# VM_Motor_v2_1.net
KiCad netlist of a schematic drawn in EAGLE
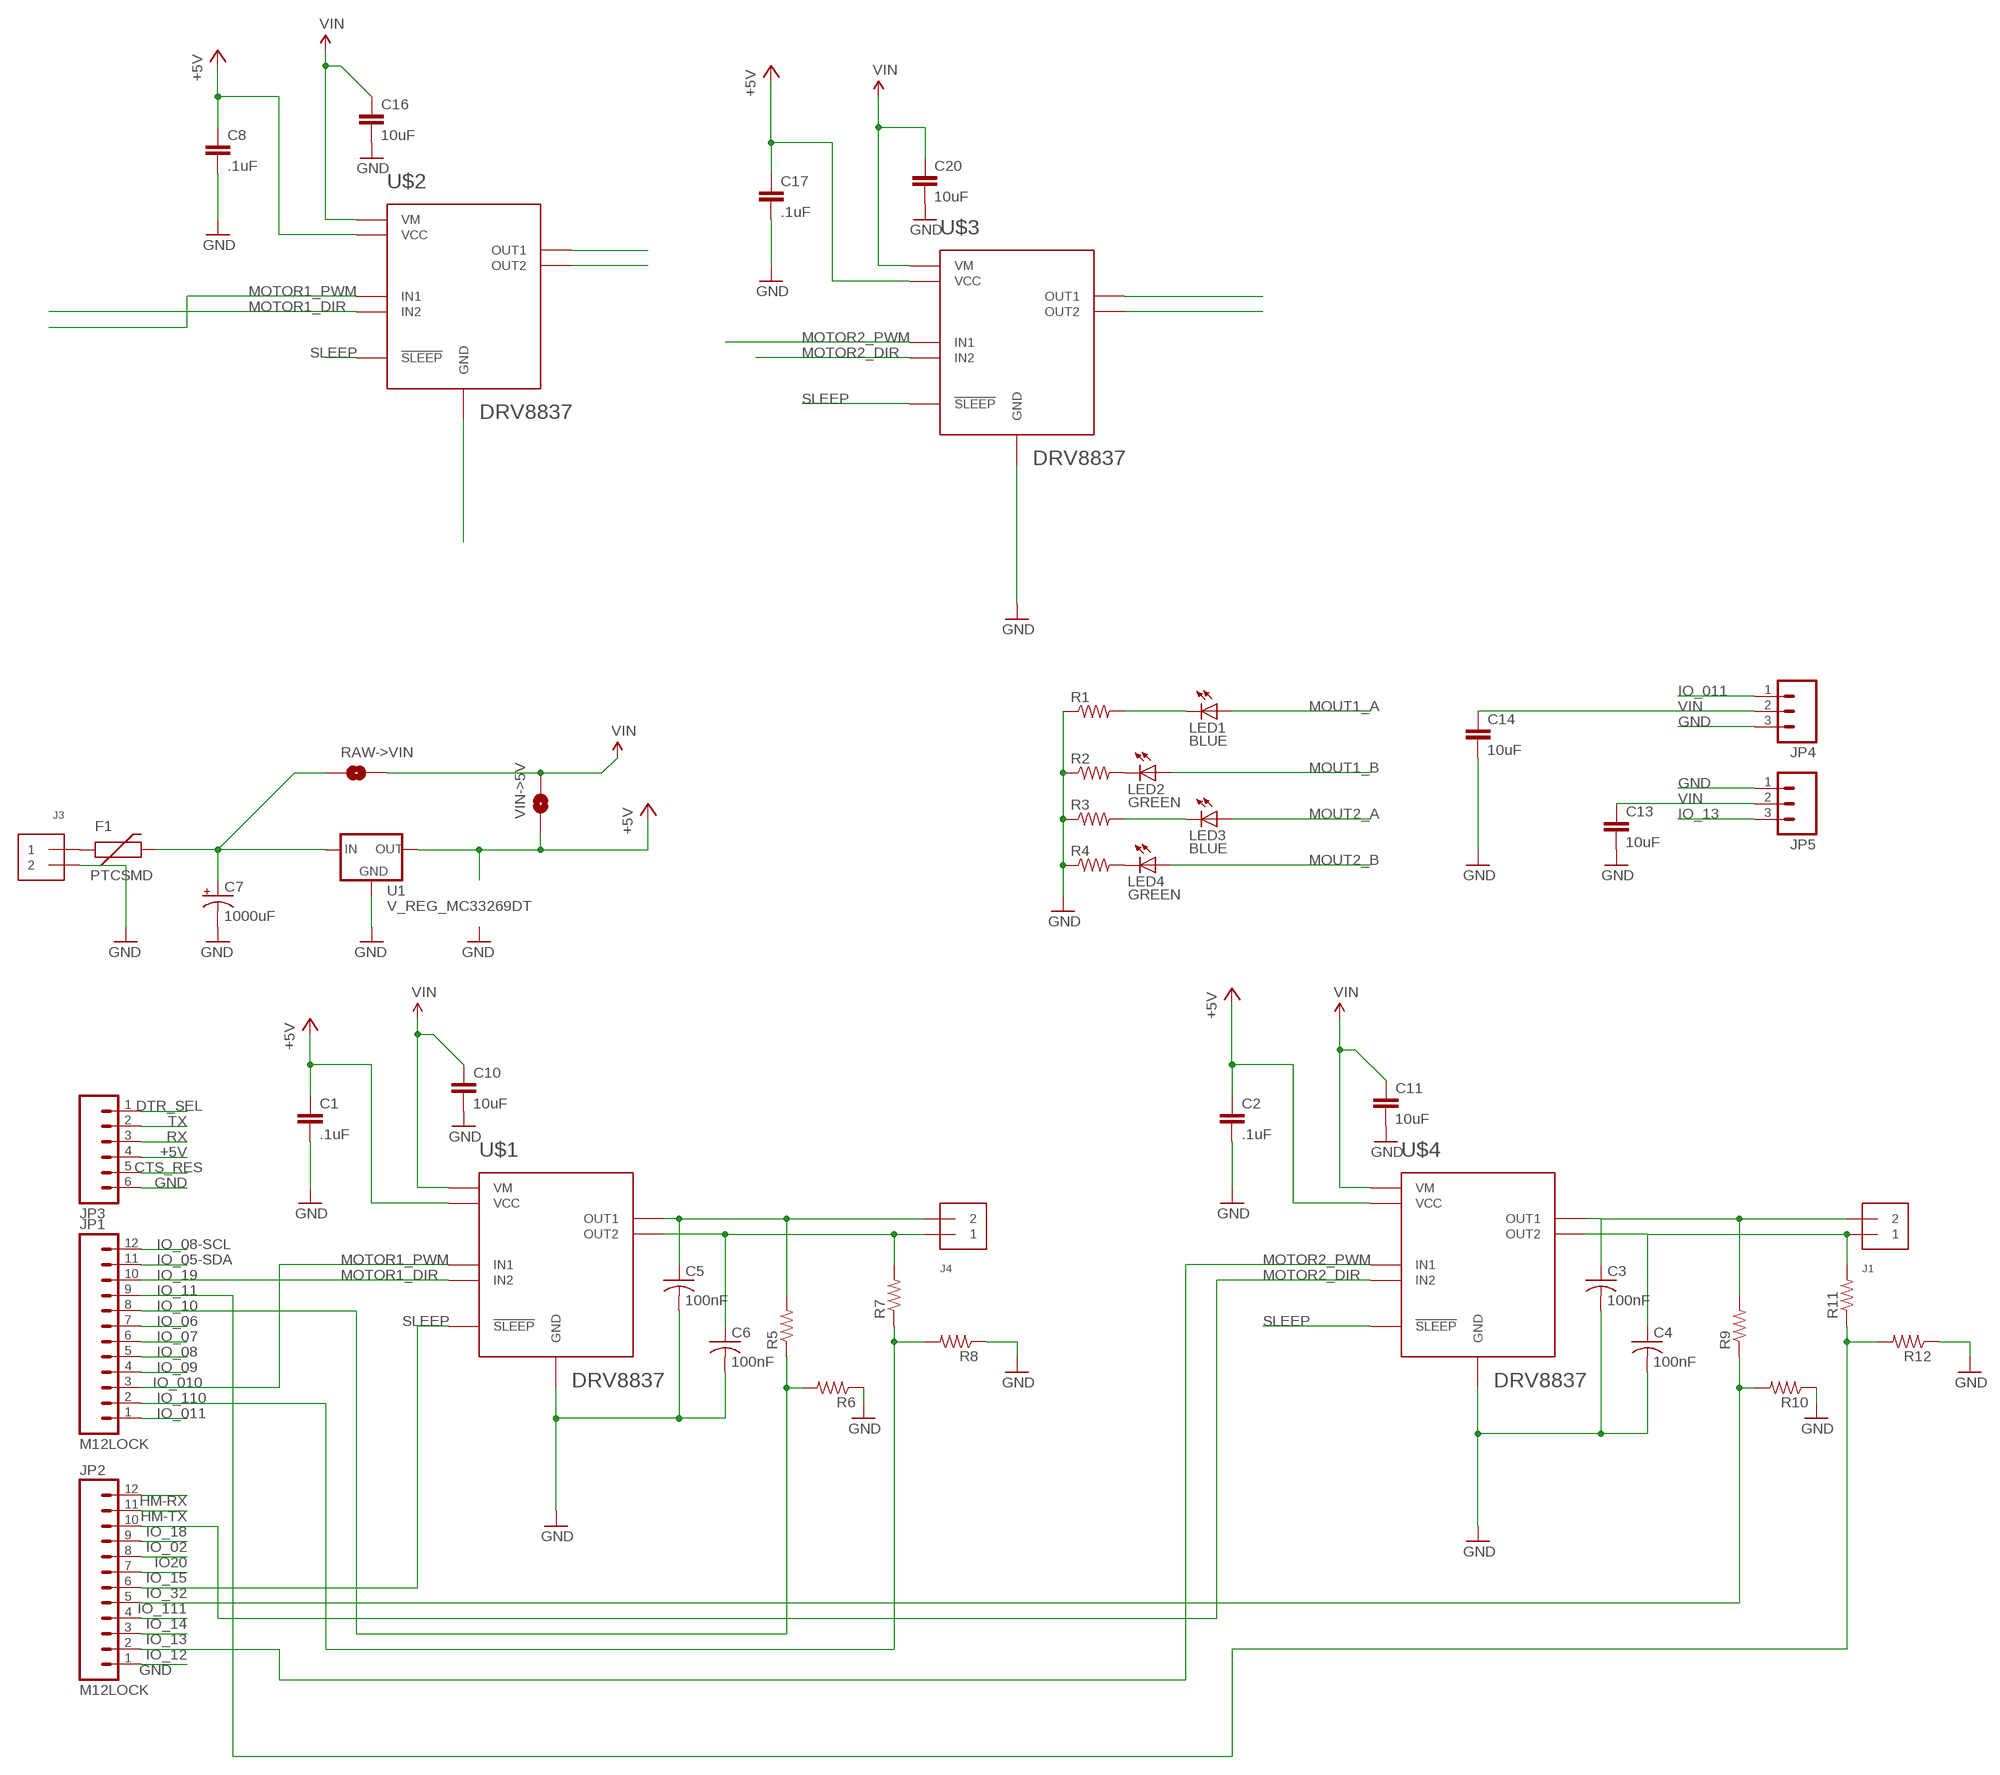
[diagram p0: schematic, sheet 1]

(export (version "E")
  (design (tool "Eeschema 10.0.6"))
  (components
    (comp (ref "C1")
      (value ".1uF")
      (footprint "eagle-import:0402-CAP")
      (libsource (lib "eagle-import") (part "CAP0402-CAP"))
    )
    (comp (ref "C2")
      (value ".1uF")
      (footprint "eagle-import:0402-CAP")
      (libsource (lib "eagle-import") (part "CAP0402-CAP"))
    )
    (comp (ref "C3")
      (value "100nF")
      (footprint "eagle-import:C0402")
      (libsource (lib "eagle-import") (part "C-USC0402"))
    )
    (comp (ref "C4")
      (value "100nF")
      (footprint "eagle-import:C0402")
      (libsource (lib "eagle-import") (part "C-USC0402"))
    )
    (comp (ref "C5")
      (value "100nF")
      (footprint "eagle-import:C0402")
      (libsource (lib "eagle-import") (part "C-USC0402"))
    )
    (comp (ref "C6")
      (value "100nF")
      (footprint "eagle-import:C0402")
      (libsource (lib "eagle-import") (part "C-USC0402"))
    )
    (comp (ref "C7")
      (value "1000uF")
      (footprint "eagle-import:150CLZ-0810")
      (libsource (lib "eagle-import") (part "CPOL-US150CLZ-0810"))
    )
    (comp (ref "C8")
      (value ".1uF")
      (footprint "eagle-import:0402-CAP")
      (libsource (lib "eagle-import") (part "CAP0402-CAP"))
    )
    (comp (ref "C10")
      (value "10uF")
      (footprint "eagle-import:0402-CAP")
      (libsource (lib "eagle-import") (part "CAP0402-CAP"))
    )
    (comp (ref "C11")
      (value "10uF")
      (footprint "eagle-import:0402-CAP")
      (libsource (lib "eagle-import") (part "CAP0402-CAP"))
    )
    (comp (ref "C13")
      (value "10uF")
      (footprint "eagle-import:0402-CAP")
      (libsource (lib "eagle-import") (part "CAP0402-CAP"))
    )
    (comp (ref "C14")
      (value "10uF")
      (footprint "eagle-import:0402-CAP")
      (libsource (lib "eagle-import") (part "CAP0402-CAP"))
    )
    (comp (ref "C16")
      (value "10uF")
      (footprint "eagle-import:0402-CAP")
      (libsource (lib "eagle-import") (part "CAP0402-CAP"))
    )
    (comp (ref "C17")
      (value ".1uF")
      (footprint "eagle-import:0402-CAP")
      (libsource (lib "eagle-import") (part "CAP0402-CAP"))
    )
    (comp (ref "C20")
      (value "10uF")
      (footprint "eagle-import:0402-CAP")
      (libsource (lib "eagle-import") (part "CAP0402-CAP"))
    )
    (comp (ref "F1")
      (value "PTCSMD")
      (footprint "eagle-import:PTC-1206")
      (libsource (lib "eagle-import") (part "PTCSMD"))
    )
    (comp (ref "J1")
      (value "TERMBLOCK_1X2")
      (footprint "eagle-import:TERMBLOCK_1X2-3.5MM")
      (libsource (lib "eagle-import") (part "TERMBLOCK_1X2"))
    )
    (comp (ref "J3")
      (value "TERMBLOCK_1X2")
      (footprint "eagle-import:TERMBLOCK_1X2-3.5MM")
      (libsource (lib "eagle-import") (part "TERMBLOCK_1X2"))
    )
    (comp (ref "J4")
      (value "TERMBLOCK_1X2")
      (footprint "eagle-import:TERMBLOCK_1X2-3.5MM")
      (libsource (lib "eagle-import") (part "TERMBLOCK_1X2"))
    )
    (comp (ref "JP1")
      (value "M12LOCK")
      (footprint "eagle-import:1X12_LOCK")
      (libsource (lib "eagle-import") (part "M12LOCK"))
    )
    (comp (ref "JP2")
      (value "M12LOCK")
      (footprint "eagle-import:1X12_LOCK")
      (libsource (lib "eagle-import") (part "M12LOCK"))
    )
    (comp (ref "JP3")
      (value "M06LOCK")
      (footprint "eagle-import:1X06_LOCK")
      (libsource (lib "eagle-import") (part "M06LOCK"))
    )
    (comp (ref "JP4")
      (value "M03LOCK")
      (footprint "eagle-import:1X03_LOCK")
      (libsource (lib "eagle-import") (part "M03LOCK"))
    )
    (comp (ref "JP5")
      (value "M03LOCK")
      (footprint "eagle-import:1X03_LOCK")
      (libsource (lib "eagle-import") (part "M03LOCK"))
    )
    (comp (ref "LED1")
      (value "BLUE")
      (footprint "eagle-import:CHIP-LED0603")
      (libsource (lib "eagle-import") (part "LEDCHIP-LED0603"))
    )
    (comp (ref "LED2")
      (value "GREEN")
      (footprint "eagle-import:CHIP-LED0603")
      (libsource (lib "eagle-import") (part "LEDCHIP-LED0603"))
    )
    (comp (ref "LED3")
      (value "BLUE")
      (footprint "eagle-import:CHIP-LED0603")
      (libsource (lib "eagle-import") (part "LEDCHIP-LED0603"))
    )
    (comp (ref "LED4")
      (value "GREEN")
      (footprint "eagle-import:CHIP-LED0603")
      (libsource (lib "eagle-import") (part "LEDCHIP-LED0603"))
    )
    (comp (ref "R1")
      (value "R-US_R0402")
      (footprint "eagle-import:R0402")
      (libsource (lib "eagle-import") (part "R-US_R0402"))
    )
    (comp (ref "R2")
      (value "R-US_R0402")
      (footprint "eagle-import:R0402")
      (libsource (lib "eagle-import") (part "R-US_R0402"))
    )
    (comp (ref "R3")
      (value "R-US_R0402")
      (footprint "eagle-import:R0402")
      (libsource (lib "eagle-import") (part "R-US_R0402"))
    )
    (comp (ref "R4")
      (value "R-US_R0402")
      (footprint "eagle-import:R0402")
      (libsource (lib "eagle-import") (part "R-US_R0402"))
    )
    (comp (ref "R5")
      (value "R-US_R0402")
      (footprint "eagle-import:R0402")
      (libsource (lib "eagle-import") (part "R-US_R0402"))
    )
    (comp (ref "R6")
      (value "R-US_R0402")
      (footprint "eagle-import:R0402")
      (libsource (lib "eagle-import") (part "R-US_R0402"))
    )
    (comp (ref "R7")
      (value "R-US_R0402")
      (footprint "eagle-import:R0402")
      (libsource (lib "eagle-import") (part "R-US_R0402"))
    )
    (comp (ref "R8")
      (value "R-US_R0402")
      (footprint "eagle-import:R0402")
      (libsource (lib "eagle-import") (part "R-US_R0402"))
    )
    (comp (ref "R9")
      (value "R-US_R0402")
      (footprint "eagle-import:R0402")
      (libsource (lib "eagle-import") (part "R-US_R0402"))
    )
    (comp (ref "R10")
      (value "R-US_R0402")
      (footprint "eagle-import:R0402")
      (libsource (lib "eagle-import") (part "R-US_R0402"))
    )
    (comp (ref "R11")
      (value "R-US_R0402")
      (footprint "eagle-import:R0402")
      (libsource (lib "eagle-import") (part "R-US_R0402"))
    )
    (comp (ref "R12")
      (value "R-US_R0402")
      (footprint "eagle-import:R0402")
      (libsource (lib "eagle-import") (part "R-US_R0402"))
    )
    (comp (ref "RAW->VIN")
      (value "SOLDERJUMPERNO")
      (footprint "eagle-import:SJ_2S-NO")
      (libsource (lib "eagle-import") (part "SOLDERJUMPERNO"))
    )
    (comp (ref "U$1")
      (value "DRV8837")
      (footprint "eagle-import:QFN8")
      (libsource (lib "eagle-import") (part "DRV8837"))
    )
    (comp (ref "U$2")
      (value "DRV8837")
      (footprint "eagle-import:QFN8")
      (libsource (lib "eagle-import") (part "DRV8837"))
    )
    (comp (ref "U$3")
      (value "DRV8837")
      (footprint "eagle-import:QFN8")
      (libsource (lib "eagle-import") (part "DRV8837"))
    )
    (comp (ref "U$4")
      (value "DRV8837")
      (footprint "eagle-import:QFN8")
      (libsource (lib "eagle-import") (part "DRV8837"))
    )
    (comp (ref "U1")
      (value "V_REG_MC33269DT")
      (footprint "eagle-import:DPAK")
      (libsource (lib "eagle-import") (part "V_REG_MC33269DT"))
    )
    (comp (ref "VIN->5V")
      (value "SOLDERJUMPERNO")
      (footprint "eagle-import:SJ_2S-NO")
      (libsource (lib "eagle-import") (part "SOLDERJUMPERNO"))
    )
  )
  (nets
    (net (code "1") (name "+5V") (class "Default")
      (node (ref "C1") (pin "1") (pinfunction "1_1") (pintype "passive"))
      (node (ref "C17") (pin "1") (pinfunction "1_1") (pintype "passive"))
      (node (ref "C2") (pin "1") (pinfunction "1_1") (pintype "passive"))
      (node (ref "C8") (pin "1") (pinfunction "1_1") (pintype "passive"))
      (node (ref "JP3") (pin "4") (pinfunction "4_4") (pintype "passive"))
      (node (ref "U$1") (pin "P$8") (pinfunction "VCC_P$8") (pintype "bidirectional"))
      (node (ref "U$2") (pin "P$8") (pinfunction "VCC_P$8") (pintype "bidirectional"))
      (node (ref "U$3") (pin "P$8") (pinfunction "VCC_P$8") (pintype "bidirectional"))
      (node (ref "U$4") (pin "P$8") (pinfunction "VCC_P$8") (pintype "bidirectional"))
      (node (ref "U1") (pin "4") (pinfunction "OUT_4") (pintype "output"))
      (node (ref "VIN->5V") (pin "1") (pinfunction "1_1") (pintype "passive"))
    )
    (net (code "2") (name "/CTS_RES") (class "Default")
      (node (ref "JP3") (pin "5") (pinfunction "5_5") (pintype "passive"))
    )
    (net (code "3") (name "/DTR_SEL") (class "Default")
      (node (ref "JP3") (pin "1") (pinfunction "1_1") (pintype "passive"))
    )
    (net (code "4") (name "/HM-RX") (class "Default")
      (node (ref "JP2") (pin "12") (pinfunction "12_12") (pintype "passive"))
    )
    (net (code "5") (name "/HM-TX") (class "Default")
      (node (ref "JP2") (pin "11") (pinfunction "11_11") (pintype "passive"))
    )
    (net (code "6") (name "/IO20") (class "Default")
      (node (ref "JP2") (pin "8") (pinfunction "8_8") (pintype "passive"))
    )
    (net (code "7") (name "/IO_02") (class "Default")
      (node (ref "JP2") (pin "9") (pinfunction "9_9") (pintype "passive"))
    )
    (net (code "8") (name "/IO_05-SDA") (class "Default")
      (node (ref "JP1") (pin "11") (pinfunction "11_11") (pintype "passive"))
    )
    (net (code "9") (name "/IO_06") (class "Default")
      (node (ref "JP1") (pin "7") (pinfunction "7_7") (pintype "passive"))
    )
    (net (code "10") (name "/IO_07") (class "Default")
      (node (ref "JP1") (pin "6") (pinfunction "6_6") (pintype "passive"))
    )
    (net (code "11") (name "/IO_08") (class "Default")
      (node (ref "JP1") (pin "5") (pinfunction "5_5") (pintype "passive"))
    )
    (net (code "12") (name "/IO_08-SCL") (class "Default")
      (node (ref "JP1") (pin "12") (pinfunction "12_12") (pintype "passive"))
    )
    (net (code "13") (name "/IO_09") (class "Default")
      (node (ref "JP1") (pin "4") (pinfunction "4_4") (pintype "passive"))
    )
    (net (code "14") (name "/IO_10") (class "Default")
      (node (ref "JP1") (pin "8") (pinfunction "8_8") (pintype "passive"))
      (node (ref "R5") (pin "1") (pinfunction "1_1") (pintype "passive"))
      (node (ref "R6") (pin "2") (pinfunction "2_2") (pintype "passive"))
    )
    (net (code "15") (name "/IO_011") (class "Default")
      (node (ref "JP1") (pin "1") (pinfunction "1_1") (pintype "passive"))
      (node (ref "JP4") (pin "1") (pinfunction "1_1") (pintype "passive"))
    )
    (net (code "16") (name "/IO_13") (class "Default")
      (node (ref "JP2") (pin "3") (pinfunction "3_3") (pintype "passive"))
      (node (ref "JP5") (pin "3") (pinfunction "3_3") (pintype "passive"))
    )
    (net (code "17") (name "/IO_14") (class "Default")
      (node (ref "JP2") (pin "4") (pinfunction "4_4") (pintype "passive"))
    )
    (net (code "18") (name "/IO_15") (class "Default")
      (node (ref "JP2") (pin "7") (pinfunction "7_7") (pintype "passive"))
    )
    (net (code "19") (name "/IO_110") (class "Default")
      (node (ref "JP1") (pin "2") (pinfunction "2_2") (pintype "passive"))
      (node (ref "R7") (pin "1") (pinfunction "1_1") (pintype "passive"))
      (node (ref "R8") (pin "2") (pinfunction "2_2") (pintype "passive"))
    )
    (net (code "20") (name "/IO_111") (class "Default")
      (node (ref "JP2") (pin "5") (pinfunction "5_5") (pintype "passive"))
      (node (ref "R10") (pin "2") (pinfunction "2_2") (pintype "passive"))
      (node (ref "R9") (pin "1") (pinfunction "1_1") (pintype "passive"))
    )
    (net (code "21") (name "/MOTOR1_DIR") (class "Default")
      (node (ref "JP1") (pin "10") (pinfunction "10_10") (pintype "passive"))
      (node (ref "U$1") (pin "P$5") (pinfunction "IN2_P$5") (pintype "bidirectional"))
      (node (ref "U$2") (pin "P$5") (pinfunction "IN2_P$5") (pintype "bidirectional"))
    )
    (net (code "22") (name "/MOTOR1_PWM") (class "Default")
      (node (ref "JP1") (pin "3") (pinfunction "3_3") (pintype "passive"))
      (node (ref "U$1") (pin "P$6") (pinfunction "IN1_P$6") (pintype "bidirectional"))
      (node (ref "U$2") (pin "P$6") (pinfunction "IN1_P$6") (pintype "bidirectional"))
    )
    (net (code "23") (name "/MOTOR2_DIR") (class "Default")
      (node (ref "JP2") (pin "10") (pinfunction "10_10") (pintype "passive"))
      (node (ref "U$3") (pin "P$5") (pinfunction "IN2_P$5") (pintype "bidirectional"))
      (node (ref "U$4") (pin "P$5") (pinfunction "IN2_P$5") (pintype "bidirectional"))
    )
    (net (code "24") (name "/MOTOR2_PWM") (class "Default")
      (node (ref "JP2") (pin "2") (pinfunction "2_2") (pintype "passive"))
      (node (ref "U$3") (pin "P$6") (pinfunction "IN1_P$6") (pintype "bidirectional"))
      (node (ref "U$4") (pin "P$6") (pinfunction "IN1_P$6") (pintype "bidirectional"))
    )
    (net (code "25") (name "/MOUT1_A") (class "Default")
      (node (ref "C5") (pin "1") (pinfunction "1_1") (pintype "passive"))
      (node (ref "J4") (pin "2") (pinfunction "2_2") (pintype "passive"))
      (node (ref "LED1") (pin "A") (pinfunction "A_A") (pintype "passive"))
      (node (ref "R5") (pin "2") (pinfunction "2_2") (pintype "passive"))
      (node (ref "U$1") (pin "P$2") (pinfunction "OUT1_P$2") (pintype "bidirectional"))
      (node (ref "U$2") (pin "P$2") (pinfunction "OUT1_P$2") (pintype "bidirectional"))
    )
    (net (code "26") (name "/MOUT1_B") (class "Default")
      (node (ref "C6") (pin "1") (pinfunction "1_1") (pintype "passive"))
      (node (ref "J4") (pin "1") (pinfunction "1_1") (pintype "passive"))
      (node (ref "LED2") (pin "A") (pinfunction "A_A") (pintype "passive"))
      (node (ref "R7") (pin "2") (pinfunction "2_2") (pintype "passive"))
      (node (ref "U$1") (pin "P$3") (pinfunction "OUT2_P$3") (pintype "bidirectional"))
      (node (ref "U$2") (pin "P$3") (pinfunction "OUT2_P$3") (pintype "bidirectional"))
    )
    (net (code "27") (name "/MOUT2_A") (class "Default")
      (node (ref "C3") (pin "1") (pinfunction "1_1") (pintype "passive"))
      (node (ref "J1") (pin "2") (pinfunction "2_2") (pintype "passive"))
      (node (ref "LED3") (pin "A") (pinfunction "A_A") (pintype "passive"))
      (node (ref "R9") (pin "2") (pinfunction "2_2") (pintype "passive"))
      (node (ref "U$3") (pin "P$2") (pinfunction "OUT1_P$2") (pintype "bidirectional"))
      (node (ref "U$4") (pin "P$2") (pinfunction "OUT1_P$2") (pintype "bidirectional"))
    )
    (net (code "28") (name "/MOUT2_B") (class "Default")
      (node (ref "C4") (pin "1") (pinfunction "1_1") (pintype "passive"))
      (node (ref "J1") (pin "1") (pinfunction "1_1") (pintype "passive"))
      (node (ref "LED4") (pin "A") (pinfunction "A_A") (pintype "passive"))
      (node (ref "R11") (pin "2") (pinfunction "2_2") (pintype "passive"))
      (node (ref "U$3") (pin "P$3") (pinfunction "OUT2_P$3") (pintype "bidirectional"))
      (node (ref "U$4") (pin "P$3") (pinfunction "OUT2_P$3") (pintype "bidirectional"))
    )
    (net (code "29") (name "/RX") (class "Default")
      (node (ref "JP3") (pin "3") (pinfunction "3_3") (pintype "passive"))
    )
    (net (code "30") (name "/SLEEP") (class "Default")
      (node (ref "JP2") (pin "6") (pinfunction "6_6") (pintype "passive"))
      (node (ref "U$1") (pin "P$7") (pinfunction "~{SLEEP}_P$7") (pintype "bidirectional"))
      (node (ref "U$2") (pin "P$7") (pinfunction "~{SLEEP}_P$7") (pintype "bidirectional"))
      (node (ref "U$3") (pin "P$7") (pinfunction "~{SLEEP}_P$7") (pintype "bidirectional"))
      (node (ref "U$4") (pin "P$7") (pinfunction "~{SLEEP}_P$7") (pintype "bidirectional"))
    )
    (net (code "31") (name "/TX") (class "Default")
      (node (ref "JP3") (pin "2") (pinfunction "2_2") (pintype "passive"))
    )
    (net (code "32") (name "GND") (class "Default")
      (node (ref "C1") (pin "2") (pinfunction "2_2") (pintype "passive"))
      (node (ref "C10") (pin "2") (pinfunction "2_2") (pintype "passive"))
      (node (ref "C11") (pin "2") (pinfunction "2_2") (pintype "passive"))
      (node (ref "C13") (pin "2") (pinfunction "2_2") (pintype "passive"))
      (node (ref "C14") (pin "2") (pinfunction "2_2") (pintype "passive"))
      (node (ref "C16") (pin "2") (pinfunction "2_2") (pintype "passive"))
      (node (ref "C17") (pin "2") (pinfunction "2_2") (pintype "passive"))
      (node (ref "C2") (pin "2") (pinfunction "2_2") (pintype "passive"))
      (node (ref "C20") (pin "2") (pinfunction "2_2") (pintype "passive"))
      (node (ref "C3") (pin "2") (pinfunction "2_2") (pintype "passive"))
      (node (ref "C4") (pin "2") (pinfunction "2_2") (pintype "passive"))
      (node (ref "C5") (pin "2") (pinfunction "2_2") (pintype "passive"))
      (node (ref "C6") (pin "2") (pinfunction "2_2") (pintype "passive"))
      (node (ref "C7") (pin "-") (pinfunction "-_-") (pintype "passive"))
      (node (ref "C8") (pin "2") (pinfunction "2_2") (pintype "passive"))
      (node (ref "J3") (pin "2") (pinfunction "2_2") (pintype "passive"))
      (node (ref "JP2") (pin "1") (pinfunction "1_1") (pintype "passive"))
      (node (ref "JP3") (pin "6") (pinfunction "6_6") (pintype "passive"))
      (node (ref "JP4") (pin "3") (pinfunction "3_3") (pintype "passive"))
      (node (ref "JP5") (pin "1") (pinfunction "1_1") (pintype "passive"))
      (node (ref "R1") (pin "1") (pinfunction "1_1") (pintype "passive"))
      (node (ref "R10") (pin "1") (pinfunction "1_1") (pintype "passive"))
      (node (ref "R12") (pin "1") (pinfunction "1_1") (pintype "passive"))
      (node (ref "R2") (pin "1") (pinfunction "1_1") (pintype "passive"))
      (node (ref "R3") (pin "1") (pinfunction "1_1") (pintype "passive"))
      (node (ref "R4") (pin "1") (pinfunction "1_1") (pintype "passive"))
      (node (ref "R6") (pin "1") (pinfunction "1_1") (pintype "passive"))
      (node (ref "R8") (pin "1") (pinfunction "1_1") (pintype "passive"))
      (node (ref "U$1") (pin "P$10") (pinfunction "GND_P$10") (pintype "bidirectional"))
      (node (ref "U$1") (pin "P$11") (pinfunction "GND_P$11") (pintype "bidirectional"))
      (node (ref "U$1") (pin "P$4") (pinfunction "GND_P$4") (pintype "bidirectional"))
      (node (ref "U$1") (pin "P$9") (pinfunction "GND_P$9") (pintype "bidirectional"))
      (node (ref "U$2") (pin "P$10") (pinfunction "GND_P$10") (pintype "bidirectional"))
      (node (ref "U$2") (pin "P$11") (pinfunction "GND_P$11") (pintype "bidirectional"))
      (node (ref "U$2") (pin "P$4") (pinfunction "GND_P$4") (pintype "bidirectional"))
      (node (ref "U$2") (pin "P$9") (pinfunction "GND_P$9") (pintype "bidirectional"))
      (node (ref "U$3") (pin "P$10") (pinfunction "GND_P$10") (pintype "bidirectional"))
      (node (ref "U$3") (pin "P$11") (pinfunction "GND_P$11") (pintype "bidirectional"))
      (node (ref "U$3") (pin "P$4") (pinfunction "GND_P$4") (pintype "bidirectional"))
      (node (ref "U$3") (pin "P$9") (pinfunction "GND_P$9") (pintype "bidirectional"))
      (node (ref "U$4") (pin "P$10") (pinfunction "GND_P$10") (pintype "bidirectional"))
      (node (ref "U$4") (pin "P$11") (pinfunction "GND_P$11") (pintype "bidirectional"))
      (node (ref "U$4") (pin "P$4") (pinfunction "GND_P$4") (pintype "bidirectional"))
      (node (ref "U$4") (pin "P$9") (pinfunction "GND_P$9") (pintype "bidirectional"))
      (node (ref "U1") (pin "1") (pinfunction "GND_1") (pintype "input"))
    )
    (net (code "33") (name "Net-(F1-Pad1)") (class "Default")
      (node (ref "F1") (pin "1") (pinfunction "1_1") (pintype "bidirectional"))
      (node (ref "J3") (pin "1") (pinfunction "1_1") (pintype "passive"))
    )
    (net (code "34") (name "Net-(JP1-Pad9)") (class "Default")
      (node (ref "JP1") (pin "9") (pinfunction "9_9") (pintype "passive"))
      (node (ref "R11") (pin "1") (pinfunction "1_1") (pintype "passive"))
      (node (ref "R12") (pin "2") (pinfunction "2_2") (pintype "passive"))
    )
    (net (code "35") (name "Net-(LED1-PadC)") (class "Default")
      (node (ref "LED1") (pin "C") (pinfunction "C_C") (pintype "passive"))
      (node (ref "R1") (pin "2") (pinfunction "2_2") (pintype "passive"))
    )
    (net (code "36") (name "Net-(LED2-PadC)") (class "Default")
      (node (ref "LED2") (pin "C") (pinfunction "C_C") (pintype "passive"))
      (node (ref "R2") (pin "2") (pinfunction "2_2") (pintype "passive"))
    )
    (net (code "37") (name "Net-(LED3-PadC)") (class "Default")
      (node (ref "LED3") (pin "C") (pinfunction "C_C") (pintype "passive"))
      (node (ref "R3") (pin "2") (pinfunction "2_2") (pintype "passive"))
    )
    (net (code "38") (name "Net-(LED4-PadC)") (class "Default")
      (node (ref "LED4") (pin "C") (pinfunction "C_C") (pintype "passive"))
      (node (ref "R4") (pin "2") (pinfunction "2_2") (pintype "passive"))
    )
    (net (code "39") (name "Net-(U1-IN)") (class "Default")
      (node (ref "C7") (pin "+") (pinfunction "+_+") (pintype "passive"))
      (node (ref "F1") (pin "2") (pinfunction "2_2") (pintype "bidirectional"))
      (node (ref "RAW->VIN") (pin "1") (pinfunction "1_1") (pintype "passive"))
      (node (ref "U1") (pin "3") (pinfunction "IN_3") (pintype "input"))
    )
    (net (code "40") (name "VIN") (class "Default")
      (node (ref "C10") (pin "1") (pinfunction "1_1") (pintype "passive"))
      (node (ref "C11") (pin "1") (pinfunction "1_1") (pintype "passive"))
      (node (ref "C13") (pin "1") (pinfunction "1_1") (pintype "passive"))
      (node (ref "C14") (pin "1") (pinfunction "1_1") (pintype "passive"))
      (node (ref "C16") (pin "1") (pinfunction "1_1") (pintype "passive"))
      (node (ref "C20") (pin "1") (pinfunction "1_1") (pintype "passive"))
      (node (ref "JP4") (pin "2") (pinfunction "2_2") (pintype "passive"))
      (node (ref "JP5") (pin "2") (pinfunction "2_2") (pintype "passive"))
      (node (ref "RAW->VIN") (pin "2") (pinfunction "2_2") (pintype "passive"))
      (node (ref "U$1") (pin "P$1") (pinfunction "VM_P$1") (pintype "bidirectional"))
      (node (ref "U$2") (pin "P$1") (pinfunction "VM_P$1") (pintype "bidirectional"))
      (node (ref "U$3") (pin "P$1") (pinfunction "VM_P$1") (pintype "bidirectional"))
      (node (ref "U$4") (pin "P$1") (pinfunction "VM_P$1") (pintype "bidirectional"))
      (node (ref "VIN->5V") (pin "2") (pinfunction "2_2") (pintype "passive"))
    )
  )
)
